# Fotocelda_01.net
KiCad netlist of a schematic drawn in EAGLE
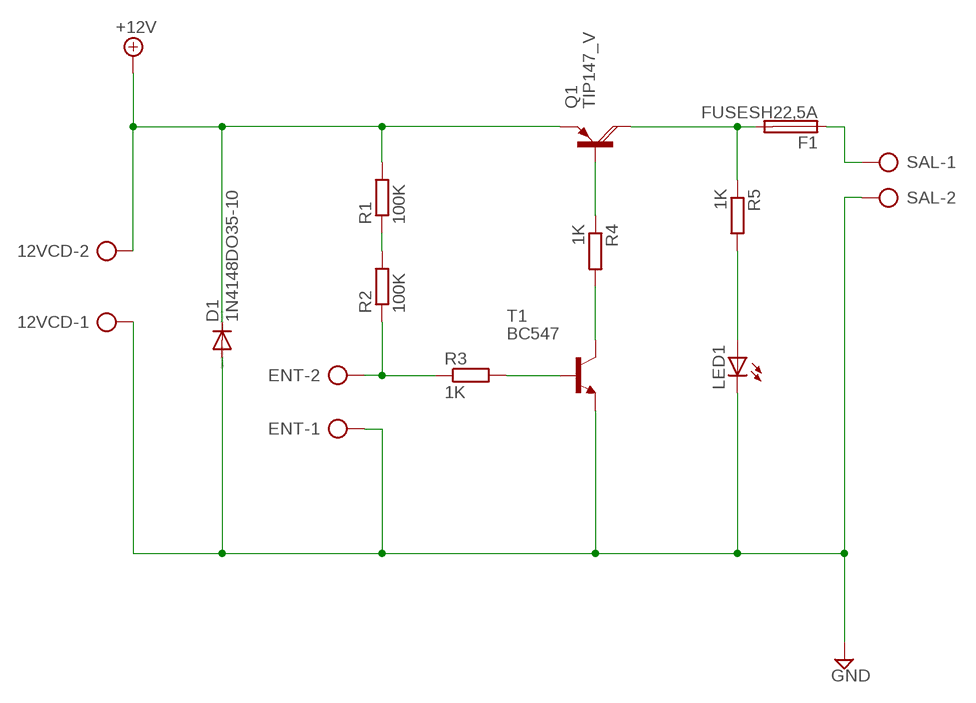
[diagram p0: schematic, sheet 1]

(export (version "E")
  (design (tool "Eeschema 10.0.6"))
  (components
    (comp (ref "12VCD")
      (value "AK500/2")
      (footprint "eagle-import:AK500_2")
      (libsource (lib "eagle-import") (part "AK500/2"))
    )
    (comp (ref "D1")
      (value "1N4148DO35-10")
      (footprint "eagle-import:DO35-10")
      (libsource (lib "eagle-import") (part "1N4148DO35-10"))
    )
    (comp (ref "ENT")
      (value "AK500/2")
      (footprint "eagle-import:AK500_2")
      (libsource (lib "eagle-import") (part "AK500/2"))
    )
    (comp (ref "F1")
      (value "FUSESH22,5A")
      (footprint "eagle-import:SH22,5A")
      (libsource (lib "eagle-import") (part "FUSESH22,5A"))
    )
    (comp (ref "LED1")
      (value "LED5MM")
      (footprint "eagle-import:LED5MM")
      (libsource (lib "eagle-import") (part "LED5MM"))
    )
    (comp (ref "Q1")
      (value "TIP147_V")
      (footprint "eagle-import:SOT93V")
      (libsource (lib "eagle-import") (part "TIP147_V"))
    )
    (comp (ref "R1")
      (value "100K")
      (footprint "eagle-import:0207_10")
      (libsource (lib "eagle-import") (part "R-EU_0207/10"))
    )
    (comp (ref "R2")
      (value "100K")
      (footprint "eagle-import:0207_10")
      (libsource (lib "eagle-import") (part "R-EU_0207/10"))
    )
    (comp (ref "R3")
      (value "1K")
      (footprint "eagle-import:0207_10")
      (libsource (lib "eagle-import") (part "R-EU_0207/10"))
    )
    (comp (ref "R4")
      (value "1K")
      (footprint "eagle-import:0207_10")
      (libsource (lib "eagle-import") (part "R-EU_0207/10"))
    )
    (comp (ref "R5")
      (value "1K")
      (footprint "eagle-import:0207_10")
      (libsource (lib "eagle-import") (part "R-EU_0207/10"))
    )
    (comp (ref "SAL")
      (value "AK500/2")
      (footprint "eagle-import:AK500_2")
      (libsource (lib "eagle-import") (part "AK500/2"))
    )
    (comp (ref "T1")
      (value "BC547")
      (footprint "eagle-import:TO92")
      (libsource (lib "eagle-import") (part "BC547"))
    )
  )
  (nets
    (net (code "1") (name "+12V") (class "Default")
      (node (ref "12VCD") (pin "2") (pinfunction "KL_2") (pintype "passive"))
      (node (ref "D1") (pin "C") (pinfunction "C_C") (pintype "passive"))
      (node (ref "Q1") (pin "E") (pinfunction "E_E") (pintype "passive"))
      (node (ref "R1") (pin "2") (pinfunction "2_2") (pintype "passive"))
    )
    (net (code "2") (name "GND") (class "Default")
      (node (ref "12VCD") (pin "1") (pinfunction "KL_1") (pintype "passive"))
      (node (ref "D1") (pin "A") (pinfunction "A_A") (pintype "passive"))
      (node (ref "ENT") (pin "1") (pinfunction "KL_1") (pintype "passive"))
      (node (ref "LED1") (pin "K") (pinfunction "C_K") (pintype "passive"))
      (node (ref "SAL") (pin "2") (pinfunction "KL_2") (pintype "passive"))
      (node (ref "T1") (pin "1") (pinfunction "E_1") (pintype "passive"))
    )
    (net (code "3") (name "Net-(ENTB-KL)") (class "Default")
      (node (ref "ENT") (pin "2") (pinfunction "KL_2") (pintype "passive"))
      (node (ref "R2") (pin "1") (pinfunction "1_1") (pintype "passive"))
      (node (ref "R3") (pin "1") (pinfunction "1_1") (pintype "passive"))
    )
    (net (code "4") (name "Net-(F1-Pad2)") (class "Default")
      (node (ref "F1") (pin "2") (pinfunction "2_2") (pintype "passive"))
      (node (ref "Q1") (pin "C") (pinfunction "C_C") (pintype "passive"))
      (node (ref "R5") (pin "1") (pinfunction "1_1") (pintype "passive"))
    )
    (net (code "5") (name "Net-(LED1-PadA)") (class "Default")
      (node (ref "LED1") (pin "A") (pinfunction "A_A") (pintype "passive"))
      (node (ref "R5") (pin "2") (pinfunction "2_2") (pintype "passive"))
    )
    (net (code "6") (name "Net-(Q1-PadB)") (class "Default")
      (node (ref "Q1") (pin "B") (pinfunction "B_B") (pintype "passive"))
      (node (ref "R4") (pin "1") (pinfunction "1_1") (pintype "passive"))
    )
    (net (code "7") (name "Net-(R1-Pad1)") (class "Default")
      (node (ref "R1") (pin "1") (pinfunction "1_1") (pintype "passive"))
      (node (ref "R2") (pin "2") (pinfunction "2_2") (pintype "passive"))
    )
    (net (code "8") (name "Net-(SALA-KL)") (class "Default")
      (node (ref "F1") (pin "1") (pinfunction "1_1") (pintype "passive"))
      (node (ref "SAL") (pin "1") (pinfunction "KL_1") (pintype "passive"))
    )
    (net (code "9") (name "Net-(T1-B)") (class "Default")
      (node (ref "R3") (pin "2") (pinfunction "2_2") (pintype "passive"))
      (node (ref "T1") (pin "2") (pinfunction "B_2") (pintype "passive"))
    )
    (net (code "10") (name "Net-(T1-C)") (class "Default")
      (node (ref "R4") (pin "2") (pinfunction "2_2") (pintype "passive"))
      (node (ref "T1") (pin "3") (pinfunction "C_3") (pintype "passive"))
    )
  )
)
